# 11-RPi.net
KiCad netlist of a schematic drawn in Altium Designer
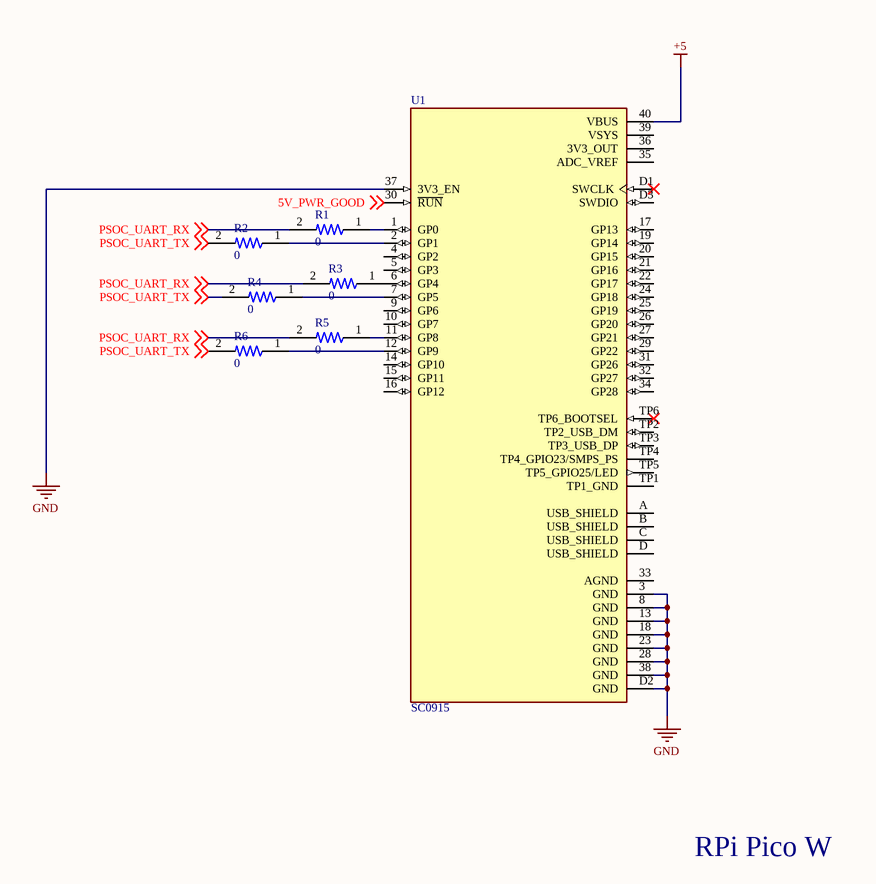
[diagram p0: 11-RPi.SchDoc]

(export (version "E")
  (design (tool "Eeschema 10.0.6"))
  (components
    (comp (ref "R1")
      (value "0")
      (footprint "RESC2012X60N")
      (description "0 Ohms Jumper 0.125W, 1/8W Chip Resistor 0805 (2012 Metric) Automotive AEC-Q200 Thick Film")
      (fields (field (name "MF") "Stackpole Electronics") (field (name "MP") "RMCF0805ZT0R00"))
      (libsource (lib "base-board") (part "RMCF0805ZT0R00"))
    )
    (comp (ref "R2")
      (value "0")
      (footprint "RESC2012X60N")
      (description "0 Ohms Jumper 0.125W, 1/8W Chip Resistor 0805 (2012 Metric) Automotive AEC-Q200 Thick Film")
      (fields (field (name "MF") "Stackpole Electronics") (field (name "MP") "RMCF0805ZT0R00"))
      (libsource (lib "base-board") (part "RMCF0805ZT0R00"))
    )
    (comp (ref "R3")
      (value "0")
      (footprint "RESC2012X60N")
      (description "0 Ohms Jumper 0.125W, 1/8W Chip Resistor 0805 (2012 Metric) Automotive AEC-Q200 Thick Film")
      (fields (field (name "MF") "Stackpole Electronics") (field (name "MP") "RMCF0805ZT0R00"))
      (libsource (lib "base-board") (part "RMCF0805ZT0R00"))
    )
    (comp (ref "R4")
      (value "0")
      (footprint "RESC2012X60N")
      (description "0 Ohms Jumper 0.125W, 1/8W Chip Resistor 0805 (2012 Metric) Automotive AEC-Q200 Thick Film")
      (fields (field (name "MF") "Stackpole Electronics") (field (name "MP") "RMCF0805ZT0R00"))
      (libsource (lib "base-board") (part "RMCF0805ZT0R00"))
    )
    (comp (ref "R5")
      (value "0")
      (footprint "RESC2012X60N")
      (description "0 Ohms Jumper 0.125W, 1/8W Chip Resistor 0805 (2012 Metric) Automotive AEC-Q200 Thick Film")
      (fields (field (name "MF") "Stackpole Electronics") (field (name "MP") "RMCF0805ZT0R00"))
      (libsource (lib "base-board") (part "RMCF0805ZT0R00"))
    )
    (comp (ref "R6")
      (value "0")
      (footprint "RESC2012X60N")
      (description "0 Ohms Jumper 0.125W, 1/8W Chip Resistor 0805 (2012 Metric) Automotive AEC-Q200 Thick Film")
      (fields (field (name "MF") "Stackpole Electronics") (field (name "MP") "RMCF0805ZT0R00"))
      (libsource (lib "base-board") (part "RMCF0805ZT0R00"))
    )
    (comp (ref "U1")
      (value "SC0915")
      (footprint "MODULE_SC0915:MODULE_SC0915")
      (description "RP2040 Raspberry Pi Pico - ARM Cortex-M0+ MCU 32-Bit Embedded Evaluation Board")
      (libsource (lib "base-board") (part "SC0915"))
    )
  )
  (nets
    (net (code "1") (name "+5") (class "Default")
      (node (ref "U1") (pin "40") (pinfunction "VBUS_40") (pintype "power_in"))
    )
    (net (code "2") (name "5V_PWR_GOOD") (class "Default")
      (node (ref "U1") (pin "30") (pinfunction "~{RUN}_30") (pintype "input"))
    )
    (net (code "3") (name "GND") (class "Default")
      (node (ref "U1") (pin "13") (pinfunction "GND_13") (pintype "power_in"))
      (node (ref "U1") (pin "18") (pinfunction "GND_18") (pintype "power_in"))
      (node (ref "U1") (pin "23") (pinfunction "GND_23") (pintype "power_in"))
      (node (ref "U1") (pin "28") (pinfunction "GND_28") (pintype "power_in"))
      (node (ref "U1") (pin "3") (pinfunction "GND_3") (pintype "power_in"))
      (node (ref "U1") (pin "37") (pinfunction "3V3_EN_37") (pintype "input"))
      (node (ref "U1") (pin "38") (pinfunction "GND_38") (pintype "power_in"))
      (node (ref "U1") (pin "8") (pinfunction "GND_8") (pintype "power_in"))
      (node (ref "U1") (pin "D2") (pinfunction "GND_D2") (pintype "power_in"))
    )
    (net (code "4") (name "Net-(U1-GP0)") (class "Default")
      (node (ref "R1") (pin "1") (pinfunction "1_1") (pintype "passive"))
      (node (ref "U1") (pin "1") (pinfunction "GP0_1") (pintype "bidirectional"))
    )
    (net (code "5") (name "Net-(U1-GP1)") (class "Default")
      (node (ref "R2") (pin "1") (pinfunction "1_1") (pintype "passive"))
      (node (ref "U1") (pin "2") (pinfunction "GP1_2") (pintype "bidirectional"))
    )
    (net (code "6") (name "Net-(U1-GP4)") (class "Default")
      (node (ref "R3") (pin "1") (pinfunction "1_1") (pintype "passive"))
      (node (ref "U1") (pin "6") (pinfunction "GP4_6") (pintype "bidirectional"))
    )
    (net (code "7") (name "Net-(U1-GP5)") (class "Default")
      (node (ref "R4") (pin "1") (pinfunction "1_1") (pintype "passive"))
      (node (ref "U1") (pin "7") (pinfunction "GP5_7") (pintype "bidirectional"))
    )
    (net (code "8") (name "Net-(U1-GP8)") (class "Default")
      (node (ref "R5") (pin "1") (pinfunction "1_1") (pintype "passive"))
      (node (ref "U1") (pin "11") (pinfunction "GP8_11") (pintype "bidirectional"))
    )
    (net (code "9") (name "Net-(U1-GP9)") (class "Default")
      (node (ref "R6") (pin "1") (pinfunction "1_1") (pintype "passive"))
      (node (ref "U1") (pin "12") (pinfunction "GP9_12") (pintype "bidirectional"))
    )
    (net (code "10") (name "PSOC_UART_RX") (class "Default")
      (node (ref "R1") (pin "2") (pinfunction "2_2") (pintype "passive"))
      (node (ref "R3") (pin "2") (pinfunction "2_2") (pintype "passive"))
      (node (ref "R5") (pin "2") (pinfunction "2_2") (pintype "passive"))
    )
    (net (code "11") (name "PSOC_UART_TX") (class "Default")
      (node (ref "R2") (pin "2") (pinfunction "2_2") (pintype "passive"))
      (node (ref "R4") (pin "2") (pinfunction "2_2") (pintype "passive"))
      (node (ref "R6") (pin "2") (pinfunction "2_2") (pintype "passive"))
    )
    (net (code "12") (name "unconnected-(U1-3V3_OUT-Pad36)") (class "Default")
      (node (ref "U1") (pin "36") (pinfunction "3V3_OUT_36") (pintype "power_in"))
    )
    (net (code "13") (name "unconnected-(U1-ADC_VREF-Pad35)") (class "Default")
      (node (ref "U1") (pin "35") (pinfunction "ADC_VREF_35") (pintype "power_in"))
    )
    (net (code "14") (name "unconnected-(U1-AGND-Pad33)") (class "Default")
      (node (ref "U1") (pin "33") (pinfunction "AGND_33") (pintype "power_in"))
    )
    (net (code "15") (name "unconnected-(U1-GP2-Pad4)") (class "Default")
      (node (ref "U1") (pin "4") (pinfunction "GP2_4") (pintype "bidirectional"))
    )
    (net (code "16") (name "unconnected-(U1-GP3-Pad5)") (class "Default")
      (node (ref "U1") (pin "5") (pinfunction "GP3_5") (pintype "bidirectional"))
    )
    (net (code "17") (name "unconnected-(U1-GP6-Pad9)") (class "Default")
      (node (ref "U1") (pin "9") (pinfunction "GP6_9") (pintype "bidirectional"))
    )
    (net (code "18") (name "unconnected-(U1-GP7-Pad10)") (class "Default")
      (node (ref "U1") (pin "10") (pinfunction "GP7_10") (pintype "bidirectional"))
    )
    (net (code "19") (name "unconnected-(U1-GP10-Pad14)") (class "Default")
      (node (ref "U1") (pin "14") (pinfunction "GP10_14") (pintype "bidirectional"))
    )
    (net (code "20") (name "unconnected-(U1-GP11-Pad15)") (class "Default")
      (node (ref "U1") (pin "15") (pinfunction "GP11_15") (pintype "bidirectional"))
    )
    (net (code "21") (name "unconnected-(U1-GP12-Pad16)") (class "Default")
      (node (ref "U1") (pin "16") (pinfunction "GP12_16") (pintype "bidirectional"))
    )
    (net (code "22") (name "unconnected-(U1-GP13-Pad17)") (class "Default")
      (node (ref "U1") (pin "17") (pinfunction "GP13_17") (pintype "bidirectional"))
    )
    (net (code "23") (name "unconnected-(U1-GP14-Pad19)") (class "Default")
      (node (ref "U1") (pin "19") (pinfunction "GP14_19") (pintype "bidirectional"))
    )
    (net (code "24") (name "unconnected-(U1-GP15-Pad20)") (class "Default")
      (node (ref "U1") (pin "20") (pinfunction "GP15_20") (pintype "bidirectional"))
    )
    (net (code "25") (name "unconnected-(U1-GP16-Pad21)") (class "Default")
      (node (ref "U1") (pin "21") (pinfunction "GP16_21") (pintype "bidirectional"))
    )
    (net (code "26") (name "unconnected-(U1-GP17-Pad22)") (class "Default")
      (node (ref "U1") (pin "22") (pinfunction "GP17_22") (pintype "bidirectional"))
    )
    (net (code "27") (name "unconnected-(U1-GP18-Pad24)") (class "Default")
      (node (ref "U1") (pin "24") (pinfunction "GP18_24") (pintype "bidirectional"))
    )
    (net (code "28") (name "unconnected-(U1-GP19-Pad25)") (class "Default")
      (node (ref "U1") (pin "25") (pinfunction "GP19_25") (pintype "bidirectional"))
    )
    (net (code "29") (name "unconnected-(U1-GP20-Pad26)") (class "Default")
      (node (ref "U1") (pin "26") (pinfunction "GP20_26") (pintype "bidirectional"))
    )
    (net (code "30") (name "unconnected-(U1-GP21-Pad27)") (class "Default")
      (node (ref "U1") (pin "27") (pinfunction "GP21_27") (pintype "bidirectional"))
    )
    (net (code "31") (name "unconnected-(U1-GP22-Pad29)") (class "Default")
      (node (ref "U1") (pin "29") (pinfunction "GP22_29") (pintype "bidirectional"))
    )
    (net (code "32") (name "unconnected-(U1-GP26-Pad31)") (class "Default")
      (node (ref "U1") (pin "31") (pinfunction "GP26_31") (pintype "bidirectional"))
    )
    (net (code "33") (name "unconnected-(U1-GP27-Pad32)") (class "Default")
      (node (ref "U1") (pin "32") (pinfunction "GP27_32") (pintype "bidirectional"))
    )
    (net (code "34") (name "unconnected-(U1-GP28-Pad34)") (class "Default")
      (node (ref "U1") (pin "34") (pinfunction "GP28_34") (pintype "bidirectional"))
    )
    (net (code "35") (name "unconnected-(U1-SWCLK-PadD1)") (class "Default")
      (node (ref "U1") (pin "D1") (pinfunction "SWCLK_D1") (pintype "input+no_connect"))
    )
    (net (code "36") (name "unconnected-(U1-SWDIO-PadD3)") (class "Default")
      (node (ref "U1") (pin "D3") (pinfunction "SWDIO_D3") (pintype "bidirectional"))
    )
    (net (code "37") (name "unconnected-(U1-TP1_GND-PadTP1)") (class "Default")
      (node (ref "U1") (pin "TP1") (pinfunction "TP1_GND_TP1") (pintype "power_in"))
    )
    (net (code "38") (name "unconnected-(U1-TP2_USB_DM-PadTP2)") (class "Default")
      (node (ref "U1") (pin "TP2") (pinfunction "TP2_USB_DM_TP2") (pintype "bidirectional"))
    )
    (net (code "39") (name "unconnected-(U1-TP3_USB_DP-PadTP3)") (class "Default")
      (node (ref "U1") (pin "TP3") (pinfunction "TP3_USB_DP_TP3") (pintype "bidirectional"))
    )
    (net (code "40") (name "unconnected-(U1-TP4_GPIO23{slash}SMPS_PS-PadTP4)") (class "Default")
      (node (ref "U1") (pin "TP4") (pinfunction "TP4_GPIO23/SMPS_PS_TP4") (pintype "passive"))
    )
    (net (code "41") (name "unconnected-(U1-TP5_GPIO25{slash}LED-PadTP5)") (class "Default")
      (node (ref "U1") (pin "TP5") (pinfunction "TP5_GPIO25/LED_TP5") (pintype "output"))
    )
    (net (code "42") (name "unconnected-(U1-TP6_BOOTSEL-PadTP6)") (class "Default")
      (node (ref "U1") (pin "TP6") (pinfunction "TP6_BOOTSEL_TP6") (pintype "input+no_connect"))
    )
    (net (code "43") (name "unconnected-(U1-USB_SHIELD-PadA)") (class "Default")
      (node (ref "U1") (pin "A") (pinfunction "USB_SHIELD_A") (pintype "power_in"))
    )
    (net (code "44") (name "unconnected-(U1-USB_SHIELD-PadB)") (class "Default")
      (node (ref "U1") (pin "B") (pinfunction "USB_SHIELD_B") (pintype "power_in"))
    )
    (net (code "45") (name "unconnected-(U1-USB_SHIELD-PadC)") (class "Default")
      (node (ref "U1") (pin "C") (pinfunction "USB_SHIELD_C") (pintype "power_in"))
    )
    (net (code "46") (name "unconnected-(U1-USB_SHIELD-PadD)") (class "Default")
      (node (ref "U1") (pin "D") (pinfunction "USB_SHIELD_D") (pintype "power_in"))
    )
    (net (code "47") (name "unconnected-(U1-VSYS-Pad39)") (class "Default")
      (node (ref "U1") (pin "39") (pinfunction "VSYS_39") (pintype "power_in"))
    )
  )
)
